# STM-ARDUINO-Power-board.net
KiCad netlist of a schematic drawn in EAGLE
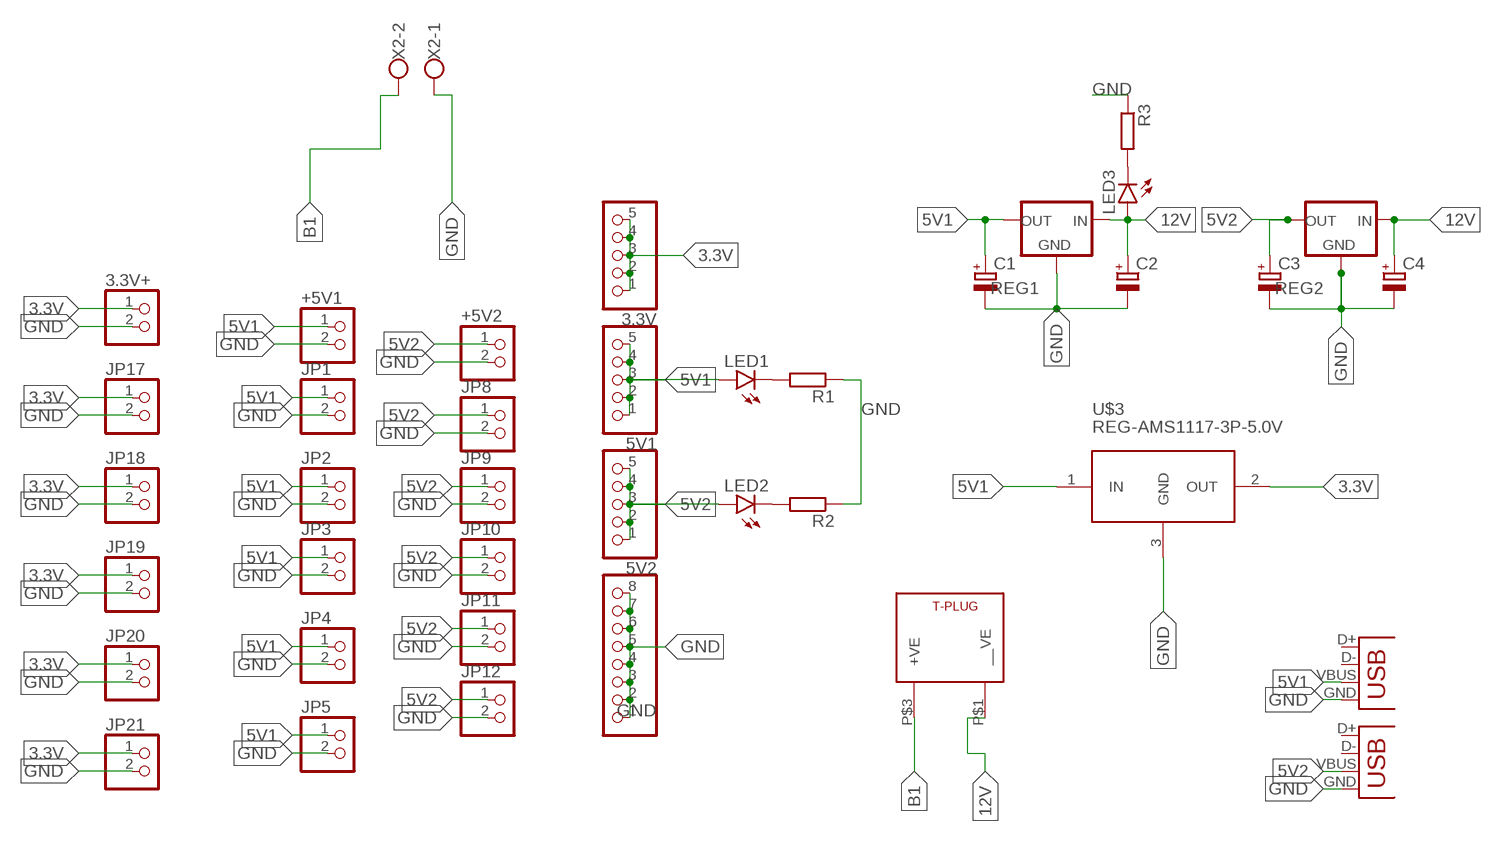
[diagram p0: schematic, sheet 1]

(export (version "E")
  (design (tool "Eeschema 10.0.6"))
  (components
    (comp (ref "+5V1")
      (value "PINHD-2_DATA")
      (footprint "eagle-import:1X02_DATA")
      (libsource (lib "eagle-import") (part "MIA_LIBRARY-2-2-2_16672108_PINHD-2_DATA"))
    )
    (comp (ref "+5V2")
      (value "PINHD-2_DATA")
      (footprint "eagle-import:1X02_DATA")
      (libsource (lib "eagle-import") (part "MIA_LIBRARY-2-2-2_16672108_PINHD-2_DATA"))
    )
    (comp (ref "3.3V")
      (value "PINHD-1X5")
      (footprint "eagle-import:1X05")
      (libsource (lib "eagle-import") (part "PINHD-1X5"))
    )
    (comp (ref "3.3V+")
      (value "PINHD-2_DATA")
      (footprint "eagle-import:1X02_DATA")
      (libsource (lib "eagle-import") (part "MIA_LIBRARY-2-2-2_16672108_PINHD-2_DATA"))
    )
    (comp (ref "5V1")
      (value "PINHD-1X5")
      (footprint "eagle-import:1X05")
      (libsource (lib "eagle-import") (part "PINHD-1X5"))
    )
    (comp (ref "5V2")
      (value "PINHD-1X5")
      (footprint "eagle-import:1X05")
      (libsource (lib "eagle-import") (part "PINHD-1X5"))
    )
    (comp (ref "C1")
      (value "CAP_POL")
      (footprint "eagle-import:E3,5-8")
      (libsource (lib "eagle-import") (part "CAP_POL"))
    )
    (comp (ref "C2")
      (value "CAP_POL")
      (footprint "eagle-import:E3,5-8")
      (libsource (lib "eagle-import") (part "CAP_POL"))
    )
    (comp (ref "C3")
      (value "CAP_POL")
      (footprint "eagle-import:E3,5-8")
      (libsource (lib "eagle-import") (part "CAP_POL"))
    )
    (comp (ref "C4")
      (value "CAP_POL")
      (footprint "eagle-import:E3,5-8")
      (libsource (lib "eagle-import") (part "CAP_POL"))
    )
    (comp (ref "GND")
      (value "PINHD-1X8")
      (footprint "eagle-import:1X08")
      (libsource (lib "eagle-import") (part "PINHD-1X8"))
    )
    (comp (ref "JP1")
      (value "PINHD-2_DATA")
      (footprint "eagle-import:1X02_DATA")
      (libsource (lib "eagle-import") (part "MIA_LIBRARY-2-2-2_16672108_PINHD-2_DATA"))
    )
    (comp (ref "JP2")
      (value "PINHD-2_DATA")
      (footprint "eagle-import:1X02_DATA")
      (libsource (lib "eagle-import") (part "MIA_LIBRARY-2-2-2_16672108_PINHD-2_DATA"))
    )
    (comp (ref "JP3")
      (value "PINHD-2_DATA")
      (footprint "eagle-import:1X02_DATA")
      (libsource (lib "eagle-import") (part "MIA_LIBRARY-2-2-2_16672108_PINHD-2_DATA"))
    )
    (comp (ref "JP4")
      (value "PINHD-2_DATA")
      (footprint "eagle-import:1X02_DATA")
      (libsource (lib "eagle-import") (part "MIA_LIBRARY-2-2-2_16672108_PINHD-2_DATA"))
    )
    (comp (ref "JP5")
      (value "PINHD-2_DATA")
      (footprint "eagle-import:1X02_DATA")
      (libsource (lib "eagle-import") (part "MIA_LIBRARY-2-2-2_16672108_PINHD-2_DATA"))
    )
    (comp (ref "JP8")
      (value "PINHD-2_DATA")
      (footprint "eagle-import:1X02_DATA")
      (libsource (lib "eagle-import") (part "MIA_LIBRARY-2-2-2_16672108_PINHD-2_DATA"))
    )
    (comp (ref "JP9")
      (value "PINHD-2_DATA")
      (footprint "eagle-import:1X02_DATA")
      (libsource (lib "eagle-import") (part "MIA_LIBRARY-2-2-2_16672108_PINHD-2_DATA"))
    )
    (comp (ref "JP10")
      (value "PINHD-2_DATA")
      (footprint "eagle-import:1X02_DATA")
      (libsource (lib "eagle-import") (part "MIA_LIBRARY-2-2-2_16672108_PINHD-2_DATA"))
    )
    (comp (ref "JP11")
      (value "PINHD-2_DATA")
      (footprint "eagle-import:1X02_DATA")
      (libsource (lib "eagle-import") (part "MIA_LIBRARY-2-2-2_16672108_PINHD-2_DATA"))
    )
    (comp (ref "JP12")
      (value "PINHD-2_DATA")
      (footprint "eagle-import:1X02_DATA")
      (libsource (lib "eagle-import") (part "PINHD-2_DATA"))
    )
    (comp (ref "JP17")
      (value "PINHD-2_DATA")
      (footprint "eagle-import:1X02_DATA")
      (libsource (lib "eagle-import") (part "MIA_LIBRARY-2-2-2_16672108_PINHD-2_DATA"))
    )
    (comp (ref "JP18")
      (value "PINHD-2_DATA")
      (footprint "eagle-import:1X02_DATA")
      (libsource (lib "eagle-import") (part "MIA_LIBRARY-2-2-2_16672108_PINHD-2_DATA"))
    )
    (comp (ref "JP19")
      (value "PINHD-2_DATA")
      (footprint "eagle-import:1X02_DATA")
      (libsource (lib "eagle-import") (part "MIA_LIBRARY-2-2-2_16672108_PINHD-2_DATA"))
    )
    (comp (ref "JP20")
      (value "PINHD-2_DATA")
      (footprint "eagle-import:1X02_DATA")
      (libsource (lib "eagle-import") (part "MIA_LIBRARY-2-2-2_16672108_PINHD-2_DATA"))
    )
    (comp (ref "JP21")
      (value "PINHD-2_DATA")
      (footprint "eagle-import:1X02_DATA")
      (libsource (lib "eagle-import") (part "MIA_LIBRARY-2-2-2_16672108_PINHD-2_DATA"))
    )
    (comp (ref "LED1")
      (value "LED5MM")
      (footprint "eagle-import:LED5MM")
      (libsource (lib "eagle-import") (part "LED5MM"))
    )
    (comp (ref "LED2")
      (value "LED5MM")
      (footprint "eagle-import:LED5MM")
      (libsource (lib "eagle-import") (part "LED5MM"))
    )
    (comp (ref "LED3")
      (value "LED5MM")
      (footprint "eagle-import:LED5MM")
      (libsource (lib "eagle-import") (part "LED5MM"))
    )
    (comp (ref "R1")
      (value "R-EU_0204/7")
      (footprint "eagle-import:0204_7")
      (libsource (lib "eagle-import") (part "R-EU_0204/7"))
    )
    (comp (ref "R2")
      (value "R-EU_0204/7")
      (footprint "eagle-import:0204_7")
      (libsource (lib "eagle-import") (part "R-EU_0204/7"))
    )
    (comp (ref "R3")
      (value "R-EU_0204/7")
      (footprint "eagle-import:0204_7")
      (libsource (lib "eagle-import") (part "R-EU_0204/7"))
    )
    (comp (ref "REG1")
      (value "78XX-METAL")
      (footprint "eagle-import:TO3-79")
      (libsource (lib "eagle-import") (part "78XX-METAL"))
    )
    (comp (ref "REG2")
      (value "78XX-METAL")
      (footprint "eagle-import:TO3-79")
      (libsource (lib "eagle-import") (part "78XX-METAL"))
    )
    (comp (ref "U$3")
      (value "REG-AMS1117-3P-5.0V")
      (footprint "eagle-import:REG-AMS1117-3P")
      (libsource (lib "eagle-import") (part "REG-AMS1117-3P-5.0V"))
    )
    (comp (ref "U$5")
      (value "T_CONNECTOR")
      (footprint "eagle-import:T-PLUG")
      (libsource (lib "eagle-import") (part "T_CONNECTOR"))
    )
    (comp (ref "USB1")
      (value "USB-A-H")
      (footprint "eagle-import:USB-A-H")
      (libsource (lib "eagle-import") (part "USB-A-H"))
    )
    (comp (ref "USB2")
      (value "USB-A-H")
      (footprint "eagle-import:USB-A-H")
      (libsource (lib "eagle-import") (part "USB-A-H"))
    )
    (comp (ref "X2")
      (value "ROSTA.POWER")
      (footprint "eagle-import:W239-302")
      (libsource (lib "eagle-import") (part "ROSTA.POWER"))
    )
  )
  (nets
    (net (code "1") (name "3.3V") (class "Default")
      (node (ref "3.3V") (pin "1") (pinfunction "1_1") (pintype "passive"))
      (node (ref "3.3V") (pin "2") (pinfunction "2_2") (pintype "passive"))
      (node (ref "3.3V") (pin "3") (pinfunction "3_3") (pintype "passive"))
      (node (ref "3.3V") (pin "4") (pinfunction "4_4") (pintype "passive"))
      (node (ref "3.3V") (pin "5") (pinfunction "5_5") (pintype "passive"))
      (node (ref "3.3V+") (pin "1") (pinfunction "1_1") (pintype "passive"))
      (node (ref "JP17") (pin "1") (pinfunction "1_1") (pintype "passive"))
      (node (ref "JP18") (pin "1") (pinfunction "1_1") (pintype "passive"))
      (node (ref "JP19") (pin "1") (pinfunction "1_1") (pintype "passive"))
      (node (ref "JP20") (pin "1") (pinfunction "1_1") (pintype "passive"))
      (node (ref "JP21") (pin "1") (pinfunction "1_1") (pintype "passive"))
      (node (ref "U$3") (pin "2") (pinfunction "OUT_2") (pintype "bidirectional"))
    )
    (net (code "2") (name "5V1") (class "Default")
      (node (ref "+5V1") (pin "1") (pinfunction "1_1") (pintype "passive"))
      (node (ref "5V1") (pin "1") (pinfunction "1_1") (pintype "passive"))
      (node (ref "5V1") (pin "2") (pinfunction "2_2") (pintype "passive"))
      (node (ref "5V1") (pin "3") (pinfunction "3_3") (pintype "passive"))
      (node (ref "5V1") (pin "4") (pinfunction "4_4") (pintype "passive"))
      (node (ref "5V1") (pin "5") (pinfunction "5_5") (pintype "passive"))
      (node (ref "C1") (pin "+") (pinfunction "+_+") (pintype "passive"))
      (node (ref "JP1") (pin "1") (pinfunction "1_1") (pintype "passive"))
      (node (ref "JP2") (pin "1") (pinfunction "1_1") (pintype "passive"))
      (node (ref "JP3") (pin "1") (pinfunction "1_1") (pintype "passive"))
      (node (ref "JP4") (pin "1") (pinfunction "1_1") (pintype "passive"))
      (node (ref "JP5") (pin "1") (pinfunction "1_1") (pintype "passive"))
      (node (ref "LED1") (pin "A") (pinfunction "A_A") (pintype "passive"))
      (node (ref "REG1") (pin "1") (pinfunction "OUT_1") (pintype "passive"))
      (node (ref "U$3") (pin "1") (pinfunction "IN_1") (pintype "bidirectional"))
      (node (ref "USB1") (pin "VBUS") (pinfunction "VBUS_VBUS") (pintype "bidirectional"))
    )
    (net (code "3") (name "5V2") (class "Default")
      (node (ref "+5V2") (pin "1") (pinfunction "1_1") (pintype "passive"))
      (node (ref "5V2") (pin "1") (pinfunction "1_1") (pintype "passive"))
      (node (ref "5V2") (pin "2") (pinfunction "2_2") (pintype "passive"))
      (node (ref "5V2") (pin "3") (pinfunction "3_3") (pintype "passive"))
      (node (ref "5V2") (pin "4") (pinfunction "4_4") (pintype "passive"))
      (node (ref "5V2") (pin "5") (pinfunction "5_5") (pintype "passive"))
      (node (ref "C3") (pin "+") (pinfunction "+_+") (pintype "passive"))
      (node (ref "JP10") (pin "1") (pinfunction "1_1") (pintype "passive"))
      (node (ref "JP11") (pin "1") (pinfunction "1_1") (pintype "passive"))
      (node (ref "JP12") (pin "1") (pinfunction "1_1") (pintype "passive"))
      (node (ref "JP8") (pin "1") (pinfunction "1_1") (pintype "passive"))
      (node (ref "JP9") (pin "1") (pinfunction "1_1") (pintype "passive"))
      (node (ref "LED2") (pin "A") (pinfunction "A_A") (pintype "passive"))
      (node (ref "REG2") (pin "1") (pinfunction "OUT_1") (pintype "passive"))
      (node (ref "USB2") (pin "VBUS") (pinfunction "VBUS_VBUS") (pintype "bidirectional"))
    )
    (net (code "4") (name "12V") (class "Default")
      (node (ref "C2") (pin "+") (pinfunction "+_+") (pintype "passive"))
      (node (ref "C4") (pin "+") (pinfunction "+_+") (pintype "passive"))
      (node (ref "LED3") (pin "A") (pinfunction "A_A") (pintype "passive"))
      (node (ref "REG1") (pin "3") (pinfunction "IN_3") (pintype "input"))
      (node (ref "REG2") (pin "3") (pinfunction "IN_3") (pintype "input"))
      (node (ref "U$5") (pin "P$1") (pinfunction "__VE_P$1") (pintype "bidirectional"))
    )
    (net (code "5") (name "B1") (class "Default")
      (node (ref "U$5") (pin "P$3") (pinfunction "+VE_P$3") (pintype "bidirectional"))
      (node (ref "X2") (pin "2") (pinfunction "KL_2") (pintype "passive"))
    )
    (net (code "6") (name "GND") (class "Default")
      (node (ref "+5V1") (pin "2") (pinfunction "2_2") (pintype "passive"))
      (node (ref "+5V2") (pin "2") (pinfunction "2_2") (pintype "passive"))
      (node (ref "3.3V+") (pin "2") (pinfunction "2_2") (pintype "passive"))
      (node (ref "C1") (pin "-") (pinfunction "-_-") (pintype "passive"))
      (node (ref "C2") (pin "-") (pinfunction "-_-") (pintype "passive"))
      (node (ref "C3") (pin "-") (pinfunction "-_-") (pintype "passive"))
      (node (ref "C4") (pin "-") (pinfunction "-_-") (pintype "passive"))
      (node (ref "GND") (pin "1") (pinfunction "1_1") (pintype "passive"))
      (node (ref "GND") (pin "2") (pinfunction "2_2") (pintype "passive"))
      (node (ref "GND") (pin "3") (pinfunction "3_3") (pintype "passive"))
      (node (ref "GND") (pin "4") (pinfunction "4_4") (pintype "passive"))
      (node (ref "GND") (pin "5") (pinfunction "5_5") (pintype "passive"))
      (node (ref "GND") (pin "6") (pinfunction "6_6") (pintype "passive"))
      (node (ref "GND") (pin "7") (pinfunction "7_7") (pintype "passive"))
      (node (ref "GND") (pin "8") (pinfunction "8_8") (pintype "passive"))
      (node (ref "JP1") (pin "2") (pinfunction "2_2") (pintype "passive"))
      (node (ref "JP10") (pin "2") (pinfunction "2_2") (pintype "passive"))
      (node (ref "JP11") (pin "2") (pinfunction "2_2") (pintype "passive"))
      (node (ref "JP12") (pin "2") (pinfunction "2_2") (pintype "passive"))
      (node (ref "JP17") (pin "2") (pinfunction "2_2") (pintype "passive"))
      (node (ref "JP18") (pin "2") (pinfunction "2_2") (pintype "passive"))
      (node (ref "JP19") (pin "2") (pinfunction "2_2") (pintype "passive"))
      (node (ref "JP2") (pin "2") (pinfunction "2_2") (pintype "passive"))
      (node (ref "JP20") (pin "2") (pinfunction "2_2") (pintype "passive"))
      (node (ref "JP21") (pin "2") (pinfunction "2_2") (pintype "passive"))
      (node (ref "JP3") (pin "2") (pinfunction "2_2") (pintype "passive"))
      (node (ref "JP4") (pin "2") (pinfunction "2_2") (pintype "passive"))
      (node (ref "JP5") (pin "2") (pinfunction "2_2") (pintype "passive"))
      (node (ref "JP8") (pin "2") (pinfunction "2_2") (pintype "passive"))
      (node (ref "JP9") (pin "2") (pinfunction "2_2") (pintype "passive"))
      (node (ref "R1") (pin "1") (pinfunction "1_1") (pintype "passive"))
      (node (ref "R2") (pin "1") (pinfunction "1_1") (pintype "passive"))
      (node (ref "R3") (pin "1") (pinfunction "1_1") (pintype "passive"))
      (node (ref "REG1") (pin "2") (pinfunction "GND_2") (pintype "input"))
      (node (ref "REG2") (pin "2") (pinfunction "GND_2") (pintype "input"))
      (node (ref "U$3") (pin "3") (pinfunction "GND_3") (pintype "bidirectional"))
      (node (ref "USB1") (pin "GND") (pinfunction "GND_GND") (pintype "bidirectional"))
      (node (ref "USB2") (pin "GND") (pinfunction "GND_GND") (pintype "bidirectional"))
      (node (ref "X2") (pin "1") (pinfunction "KL_1") (pintype "passive"))
    )
    (net (code "7") (name "Net-(LED1-C)") (class "Default")
      (node (ref "LED1") (pin "K") (pinfunction "C_K") (pintype "passive"))
      (node (ref "R1") (pin "2") (pinfunction "2_2") (pintype "passive"))
    )
    (net (code "8") (name "Net-(LED2-C)") (class "Default")
      (node (ref "LED2") (pin "K") (pinfunction "C_K") (pintype "passive"))
      (node (ref "R2") (pin "2") (pinfunction "2_2") (pintype "passive"))
    )
    (net (code "9") (name "Net-(LED3-C)") (class "Default")
      (node (ref "LED3") (pin "K") (pinfunction "C_K") (pintype "passive"))
      (node (ref "R3") (pin "2") (pinfunction "2_2") (pintype "passive"))
    )
    (net (code "10") (name "unconnected-(USB1-PadD+)") (class "Default")
      (node (ref "USB1") (pin "D+") (pinfunction "D+_D+") (pintype "bidirectional"))
    )
    (net (code "11") (name "unconnected-(USB1-PadD-)") (class "Default")
      (node (ref "USB1") (pin "D-") (pinfunction "D-_D-") (pintype "bidirectional"))
    )
    (net (code "12") (name "unconnected-(USB2-PadD+)") (class "Default")
      (node (ref "USB2") (pin "D+") (pinfunction "D+_D+") (pintype "bidirectional"))
    )
    (net (code "13") (name "unconnected-(USB2-PadD-)") (class "Default")
      (node (ref "USB2") (pin "D-") (pinfunction "D-_D-") (pintype "bidirectional"))
    )
  )
)
